# CANLink_revA.net
KiCad netlist of a schematic drawn in Altium Designer
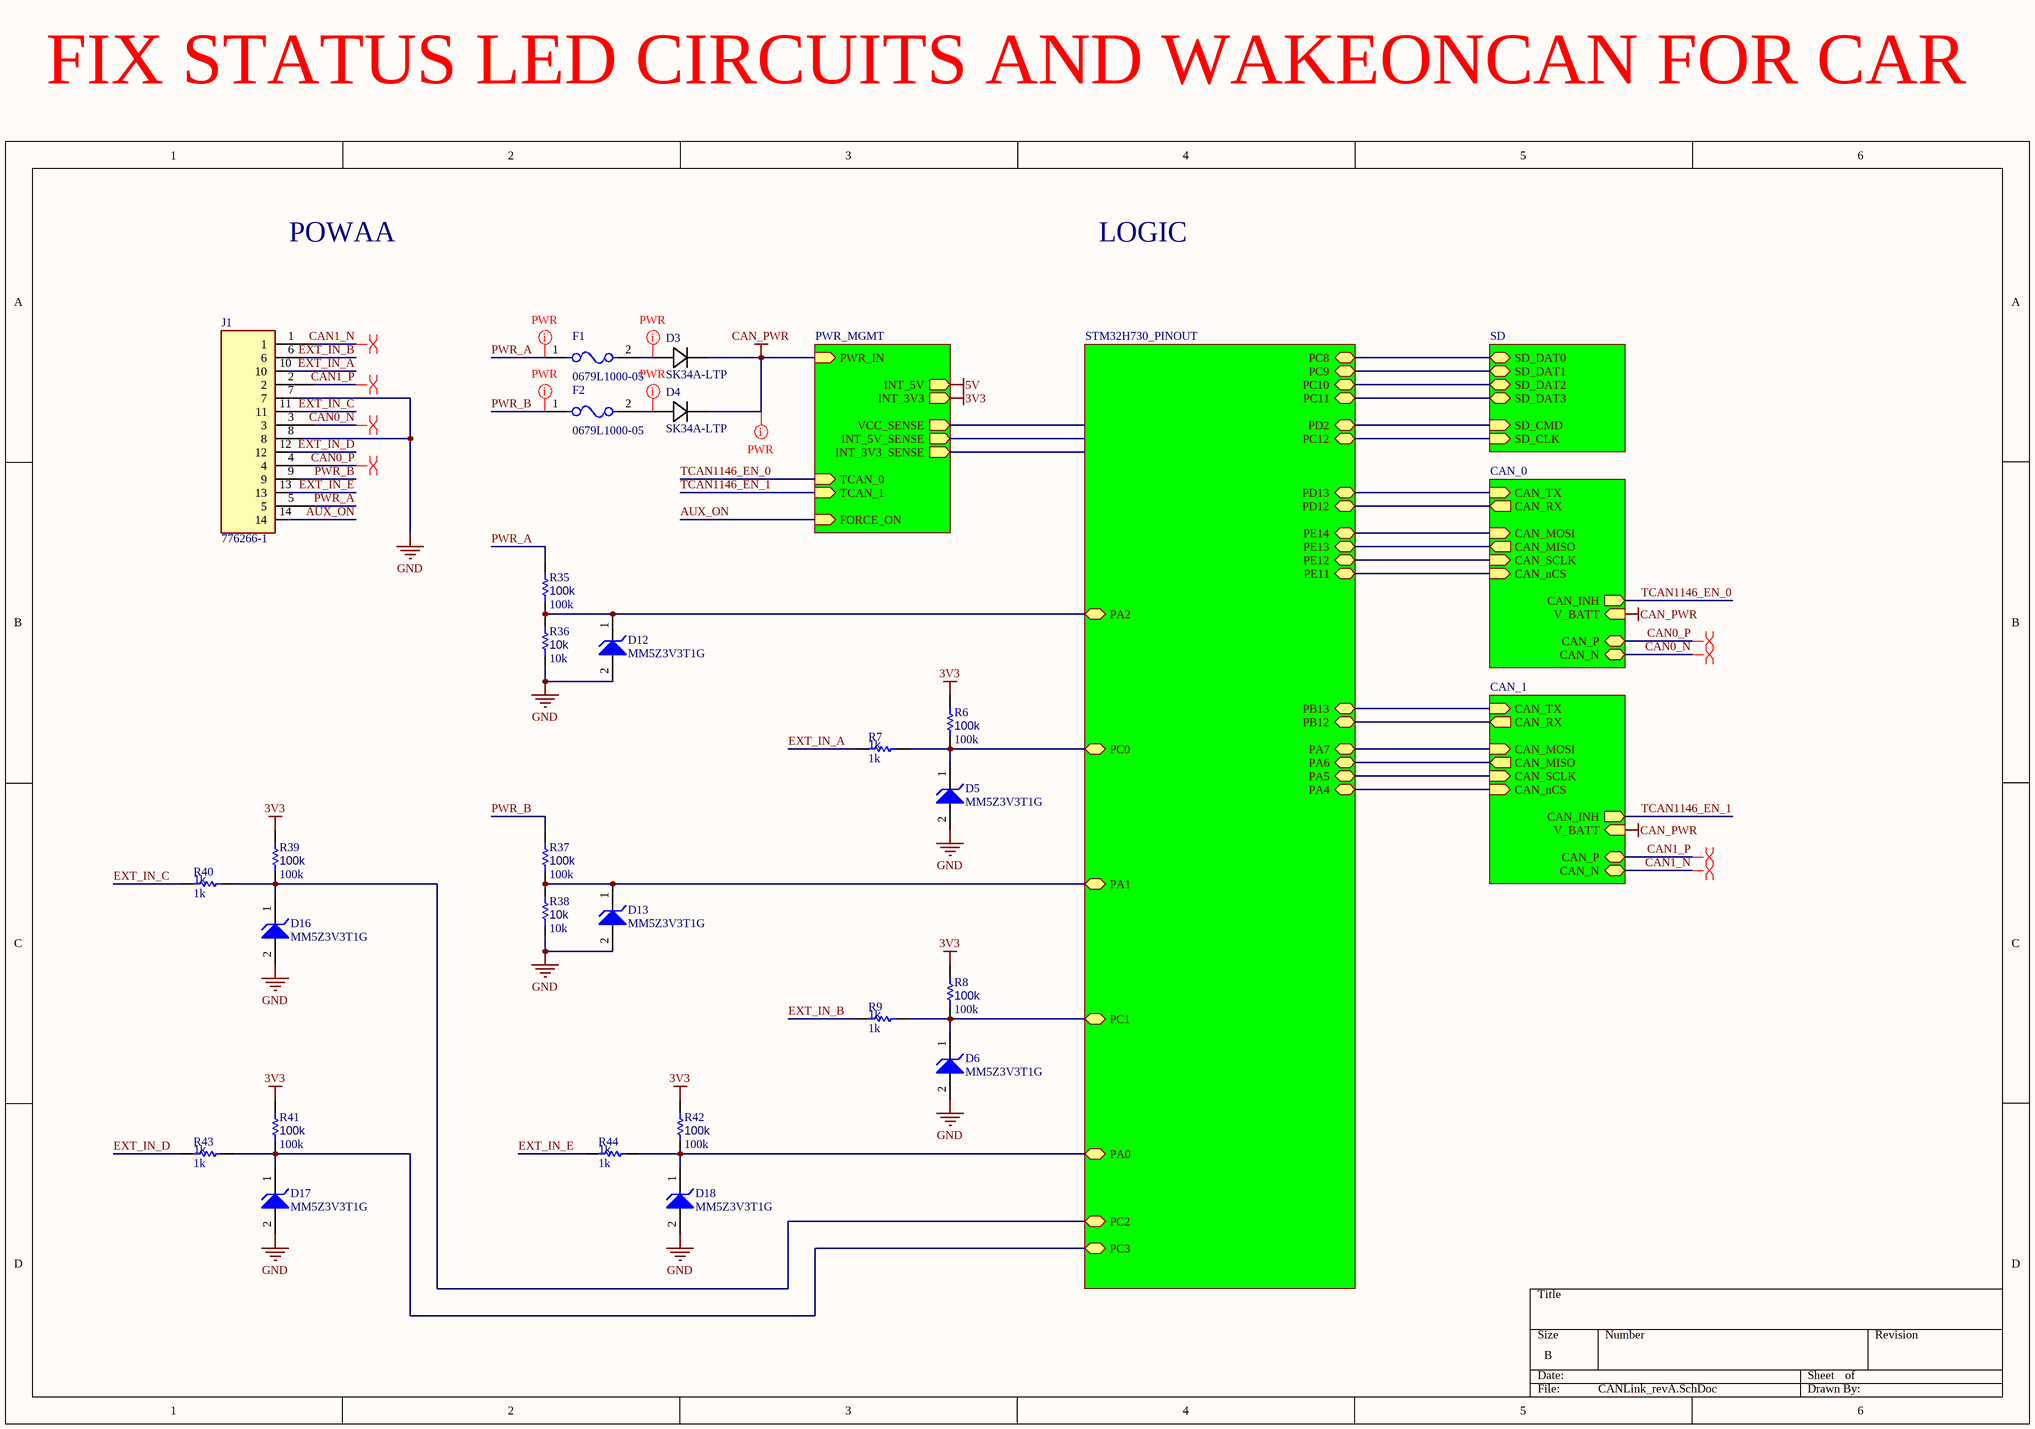
[diagram p0: CANLink_revA.SchDoc]

(export (version "E")
  (design (tool "Eeschema 10.0.6"))
  (components
    (comp (ref "D3")
      (value "SK34A-LTP")
      (footprint "SK34A-LTP-Footprint-1")
      (description "Rectifier Diode, Schottky, 1 Phase, 1 Element, 3A, 40V V(RRM), Silicon, DO-214AC")
      (libsource (lib "Space Concordia") (part "SK34A-LTP"))
    )
    (comp (ref "D4")
      (value "SK34A-LTP")
      (footprint "SK34A-LTP-Footprint-1")
      (description "Rectifier Diode, Schottky, 1 Phase, 1 Element, 3A, 40V V(RRM), Silicon, DO-214AC")
      (libsource (lib "Space Concordia") (part "SK34A-LTP"))
    )
    (comp (ref "D5")
      (value "MM5Z3V3T1G")
      (footprint "ONSC-SOD-523-2-502-01_V")
      (description "Zener Voltage Regulator, 500 mW, 2-Pin SOD-523, Pb-Free, Tape and Reel")
      (fields (field (name "MANUFACTURER") "On Semiconductor"))
      (libsource (lib "Altium Content Vault") (part "ONSC-K1A2-2"))
    )
    (comp (ref "D6")
      (value "MM5Z3V3T1G")
      (footprint "ONSC-SOD-523-2-502-01_V")
      (description "Zener Voltage Regulator, 500 mW, 2-Pin SOD-523, Pb-Free, Tape and Reel")
      (fields (field (name "MANUFACTURER") "On Semiconductor"))
      (libsource (lib "Altium Content Vault") (part "ONSC-K1A2-2"))
    )
    (comp (ref "D12")
      (value "MM5Z3V3T1G")
      (footprint "ONSC-SOD-523-2-502-01_V")
      (description "Zener Voltage Regulator, 500 mW, 2-Pin SOD-523, Pb-Free, Tape and Reel")
      (fields (field (name "MANUFACTURER") "On Semiconductor"))
      (libsource (lib "Altium Content Vault") (part "ONSC-K1A2-2"))
    )
    (comp (ref "D13")
      (value "MM5Z3V3T1G")
      (footprint "ONSC-SOD-523-2-502-01_V")
      (description "Zener Voltage Regulator, 500 mW, 2-Pin SOD-523, Pb-Free, Tape and Reel")
      (fields (field (name "MANUFACTURER") "On Semiconductor"))
      (libsource (lib "Altium Content Vault") (part "ONSC-K1A2-2"))
    )
    (comp (ref "D16")
      (value "MM5Z3V3T1G")
      (footprint "ONSC-SOD-523-2-502-01_V")
      (description "Zener Voltage Regulator, 500 mW, 2-Pin SOD-523, Pb-Free, Tape and Reel")
      (fields (field (name "MANUFACTURER") "On Semiconductor"))
      (libsource (lib "Altium Content Vault") (part "ONSC-K1A2-2"))
    )
    (comp (ref "D17")
      (value "MM5Z3V3T1G")
      (footprint "ONSC-SOD-523-2-502-01_V")
      (description "Zener Voltage Regulator, 500 mW, 2-Pin SOD-523, Pb-Free, Tape and Reel")
      (fields (field (name "MANUFACTURER") "On Semiconductor"))
      (libsource (lib "Altium Content Vault") (part "ONSC-K1A2-2"))
    )
    (comp (ref "D18")
      (value "MM5Z3V3T1G")
      (footprint "ONSC-SOD-523-2-502-01_V")
      (description "Zener Voltage Regulator, 500 mW, 2-Pin SOD-523, Pb-Free, Tape and Reel")
      (fields (field (name "MANUFACTURER") "On Semiconductor"))
      (libsource (lib "Altium Content Vault") (part "ONSC-K1A2-2"))
    )
    (comp (ref "F1")
      (value "0679L1000-05")
      (footprint "FP-0679L-MFG")
      (description "DIFF P#!!!\r\n\r\nFUSE BRD MNT 1A 125VAC/VDC")
      (fields
        (field (name "OCTOPART") "https://octopart.com/0679l9150-01-bel+fuse-70850665")
        (field (name "MANUFACTURER") "Bel Fuse")
      )
      (libsource (lib "Altium Content Vault") (part "5bcf9b9f640e542cf0359d10258e979"))
    )
    (comp (ref "F2")
      (value "0679L1000-05")
      (footprint "FP-0679L-MFG")
      (description "DIFF P#!!!\r\n\r\nFUSE BRD MNT 1A 125VAC/VDC")
      (fields
        (field (name "OCTOPART") "https://octopart.com/0679l9150-01-bel+fuse-70850665")
        (field (name "MANUFACTURER") "Bel Fuse")
      )
      (libsource (lib "Altium Content Vault") (part "5bcf9b9f640e542cf0359d10258e979"))
    )
    (comp (ref "J1")
      (value "776266-1")
      (footprint "776266-1-Footprint-1")
      (description "Board Connector")
      (libsource (lib "Space Concordia") (part "776266-1"))
    )
    (comp (ref "R6")
      (value "100k")
      (footprint "R0603B")
      (description "Resistor")
      (fields (field (name "ALTIUM_VALUE") "100k"))
      (libsource (lib "Space Concordia") (part "Resistor"))
    )
    (comp (ref "R7")
      (value "1k")
      (footprint "R0603B")
      (description "Resistor")
      (fields (field (name "ALTIUM_VALUE") "1k"))
      (libsource (lib "Space Concordia") (part "Resistor"))
    )
    (comp (ref "R8")
      (value "100k")
      (footprint "R0603B")
      (description "Resistor")
      (fields (field (name "ALTIUM_VALUE") "100k"))
      (libsource (lib "Space Concordia") (part "Resistor"))
    )
    (comp (ref "R9")
      (value "1k")
      (footprint "R0603B")
      (description "Resistor")
      (fields (field (name "ALTIUM_VALUE") "1k"))
      (libsource (lib "Space Concordia") (part "Resistor"))
    )
    (comp (ref "R35")
      (value "100k")
      (footprint "R0603B")
      (description "Resistor")
      (fields (field (name "ALTIUM_VALUE") "100k"))
      (libsource (lib "Space Concordia") (part "Resistor"))
    )
    (comp (ref "R36")
      (value "10k")
      (footprint "R0603B")
      (description "Resistor")
      (fields (field (name "ALTIUM_VALUE") "10k"))
      (libsource (lib "Space Concordia") (part "Resistor"))
    )
    (comp (ref "R37")
      (value "100k")
      (footprint "R0603B")
      (description "Resistor")
      (fields (field (name "ALTIUM_VALUE") "100k"))
      (libsource (lib "Space Concordia") (part "Resistor"))
    )
    (comp (ref "R38")
      (value "10k")
      (footprint "R0603B")
      (description "Resistor")
      (fields (field (name "ALTIUM_VALUE") "10k"))
      (libsource (lib "Space Concordia") (part "Resistor"))
    )
    (comp (ref "R39")
      (value "100k")
      (footprint "R0603B")
      (description "Resistor")
      (fields (field (name "ALTIUM_VALUE") "100k"))
      (libsource (lib "Space Concordia") (part "Resistor"))
    )
    (comp (ref "R40")
      (value "1k")
      (footprint "R0603B")
      (description "Resistor")
      (fields (field (name "ALTIUM_VALUE") "1k"))
      (libsource (lib "Space Concordia") (part "Resistor"))
    )
    (comp (ref "R41")
      (value "100k")
      (footprint "R0603B")
      (description "Resistor")
      (fields (field (name "ALTIUM_VALUE") "100k"))
      (libsource (lib "Space Concordia") (part "Resistor"))
    )
    (comp (ref "R42")
      (value "100k")
      (footprint "R0603B")
      (description "Resistor")
      (fields (field (name "ALTIUM_VALUE") "100k"))
      (libsource (lib "Space Concordia") (part "Resistor"))
    )
    (comp (ref "R43")
      (value "1k")
      (footprint "R0603B")
      (description "Resistor")
      (fields (field (name "ALTIUM_VALUE") "1k"))
      (libsource (lib "Space Concordia") (part "Resistor"))
    )
    (comp (ref "R44")
      (value "1k")
      (footprint "R0603B")
      (description "Resistor")
      (fields (field (name "ALTIUM_VALUE") "1k"))
      (libsource (lib "Space Concordia") (part "Resistor"))
    )
  )
  (nets
    (net (code "1") (name "/AUX_ON") (class "Default")
      (node (ref "J1") (pin "14") (pinfunction "14_14") (pintype "passive"))
    )
    (net (code "2") (name "/CAN0_N") (class "Default")
      (node (ref "J1") (pin "3") (pinfunction "3_3") (pintype "passive"))
    )
    (net (code "3") (name "/CAN0_P") (class "Default")
      (node (ref "J1") (pin "4") (pinfunction "4_4") (pintype "passive"))
    )
    (net (code "4") (name "/CAN1_N") (class "Default")
      (node (ref "J1") (pin "1") (pinfunction "1_1") (pintype "passive"))
    )
    (net (code "5") (name "/CAN1_P") (class "Default")
      (node (ref "J1") (pin "2") (pinfunction "2_2") (pintype "passive"))
    )
    (net (code "18") (name "/EXT_IN_A") (class "Default")
      (node (ref "J1") (pin "10") (pinfunction "10_10") (pintype "passive"))
      (node (ref "R7") (pin "2") (pinfunction "2_2") (pintype "passive"))
    )
    (net (code "19") (name "/EXT_IN_B") (class "Default")
      (node (ref "J1") (pin "6") (pinfunction "6_6") (pintype "passive"))
      (node (ref "R9") (pin "2") (pinfunction "2_2") (pintype "passive"))
    )
    (net (code "20") (name "/EXT_IN_C") (class "Default")
      (node (ref "J1") (pin "11") (pinfunction "11_11") (pintype "passive"))
      (node (ref "R40") (pin "2") (pinfunction "2_2") (pintype "passive"))
    )
    (net (code "21") (name "/EXT_IN_D") (class "Default")
      (node (ref "J1") (pin "12") (pinfunction "12_12") (pintype "passive"))
      (node (ref "R43") (pin "2") (pinfunction "2_2") (pintype "passive"))
    )
    (net (code "22") (name "/EXT_IN_E") (class "Default")
      (node (ref "J1") (pin "13") (pinfunction "13_13") (pintype "passive"))
      (node (ref "R44") (pin "2") (pinfunction "2_2") (pintype "passive"))
    )
    (net (code "25") (name "/PA0") (class "Default")
      (node (ref "D18") (pin "1") (pinfunction "K_1") (pintype "passive"))
      (node (ref "R42") (pin "2") (pinfunction "2_2") (pintype "passive"))
      (node (ref "R44") (pin "1") (pinfunction "1_1") (pintype "passive"))
    )
    (net (code "26") (name "/PA1") (class "Default")
      (node (ref "D13") (pin "1") (pinfunction "K_1") (pintype "passive"))
      (node (ref "R37") (pin "2") (pinfunction "2_2") (pintype "passive"))
      (node (ref "R38") (pin "1") (pinfunction "1_1") (pintype "passive"))
    )
    (net (code "27") (name "/PA2") (class "Default")
      (node (ref "D12") (pin "1") (pinfunction "K_1") (pintype "passive"))
      (node (ref "R35") (pin "2") (pinfunction "2_2") (pintype "passive"))
      (node (ref "R36") (pin "1") (pinfunction "1_1") (pintype "passive"))
    )
    (net (code "28") (name "/PC0") (class "Default")
      (node (ref "D5") (pin "1") (pinfunction "K_1") (pintype "passive"))
      (node (ref "R6") (pin "2") (pinfunction "2_2") (pintype "passive"))
      (node (ref "R7") (pin "1") (pinfunction "1_1") (pintype "passive"))
    )
    (net (code "29") (name "/PC1") (class "Default")
      (node (ref "D6") (pin "1") (pinfunction "K_1") (pintype "passive"))
      (node (ref "R8") (pin "2") (pinfunction "2_2") (pintype "passive"))
      (node (ref "R9") (pin "1") (pinfunction "1_1") (pintype "passive"))
    )
    (net (code "30") (name "/PC2") (class "Default")
      (node (ref "D16") (pin "1") (pinfunction "K_1") (pintype "passive"))
      (node (ref "R39") (pin "2") (pinfunction "2_2") (pintype "passive"))
      (node (ref "R40") (pin "1") (pinfunction "1_1") (pintype "passive"))
    )
    (net (code "31") (name "/PC3") (class "Default")
      (node (ref "D17") (pin "1") (pinfunction "K_1") (pintype "passive"))
      (node (ref "R41") (pin "2") (pinfunction "2_2") (pintype "passive"))
      (node (ref "R43") (pin "1") (pinfunction "1_1") (pintype "passive"))
    )
    (net (code "38") (name "/PWR_A") (class "Default")
      (node (ref "F1") (pin "1") (pinfunction "1_1") (pintype "passive"))
      (node (ref "J1") (pin "5") (pinfunction "5_5") (pintype "passive"))
      (node (ref "R35") (pin "1") (pinfunction "1_1") (pintype "passive"))
    )
    (net (code "39") (name "/PWR_B") (class "Default")
      (node (ref "F2") (pin "1") (pinfunction "1_1") (pintype "passive"))
      (node (ref "J1") (pin "9") (pinfunction "9_9") (pintype "passive"))
      (node (ref "R37") (pin "1") (pinfunction "1_1") (pintype "passive"))
    )
    (net (code "43") (name "3V3") (class "Default")
      (node (ref "R39") (pin "1") (pinfunction "1_1") (pintype "passive"))
      (node (ref "R41") (pin "1") (pinfunction "1_1") (pintype "passive"))
      (node (ref "R42") (pin "1") (pinfunction "1_1") (pintype "passive"))
      (node (ref "R6") (pin "1") (pinfunction "1_1") (pintype "passive"))
      (node (ref "R8") (pin "1") (pinfunction "1_1") (pintype "passive"))
    )
    (net (code "45") (name "CAN_PWR") (class "Default")
      (node (ref "D3") (pin "1") (pinfunction "CATHODE_1") (pintype "passive"))
      (node (ref "D4") (pin "1") (pinfunction "CATHODE_1") (pintype "passive"))
    )
    (net (code "46") (name "GND") (class "Default")
      (node (ref "D12") (pin "2") (pinfunction "A_2") (pintype "passive"))
      (node (ref "D13") (pin "2") (pinfunction "A_2") (pintype "passive"))
      (node (ref "D16") (pin "2") (pinfunction "A_2") (pintype "passive"))
      (node (ref "D17") (pin "2") (pinfunction "A_2") (pintype "passive"))
      (node (ref "D18") (pin "2") (pinfunction "A_2") (pintype "passive"))
      (node (ref "D5") (pin "2") (pinfunction "A_2") (pintype "passive"))
      (node (ref "D6") (pin "2") (pinfunction "A_2") (pintype "passive"))
      (node (ref "J1") (pin "7") (pinfunction "7_7") (pintype "passive"))
      (node (ref "J1") (pin "8") (pinfunction "8_8") (pintype "passive"))
      (node (ref "R36") (pin "2") (pinfunction "2_2") (pintype "passive"))
      (node (ref "R38") (pin "2") (pinfunction "2_2") (pintype "passive"))
    )
    (net (code "47") (name "Net-(D3-ANODE)") (class "Default")
      (node (ref "D3") (pin "2") (pinfunction "ANODE_2") (pintype "passive"))
      (node (ref "F1") (pin "2") (pinfunction "2_2") (pintype "passive"))
    )
    (net (code "48") (name "Net-(D4-ANODE)") (class "Default")
      (node (ref "D4") (pin "2") (pinfunction "ANODE_2") (pintype "passive"))
      (node (ref "F2") (pin "2") (pinfunction "2_2") (pintype "passive"))
    )
  )
)
